# input_output.net
KiCad netlist of a schematic drawn in EAGLE
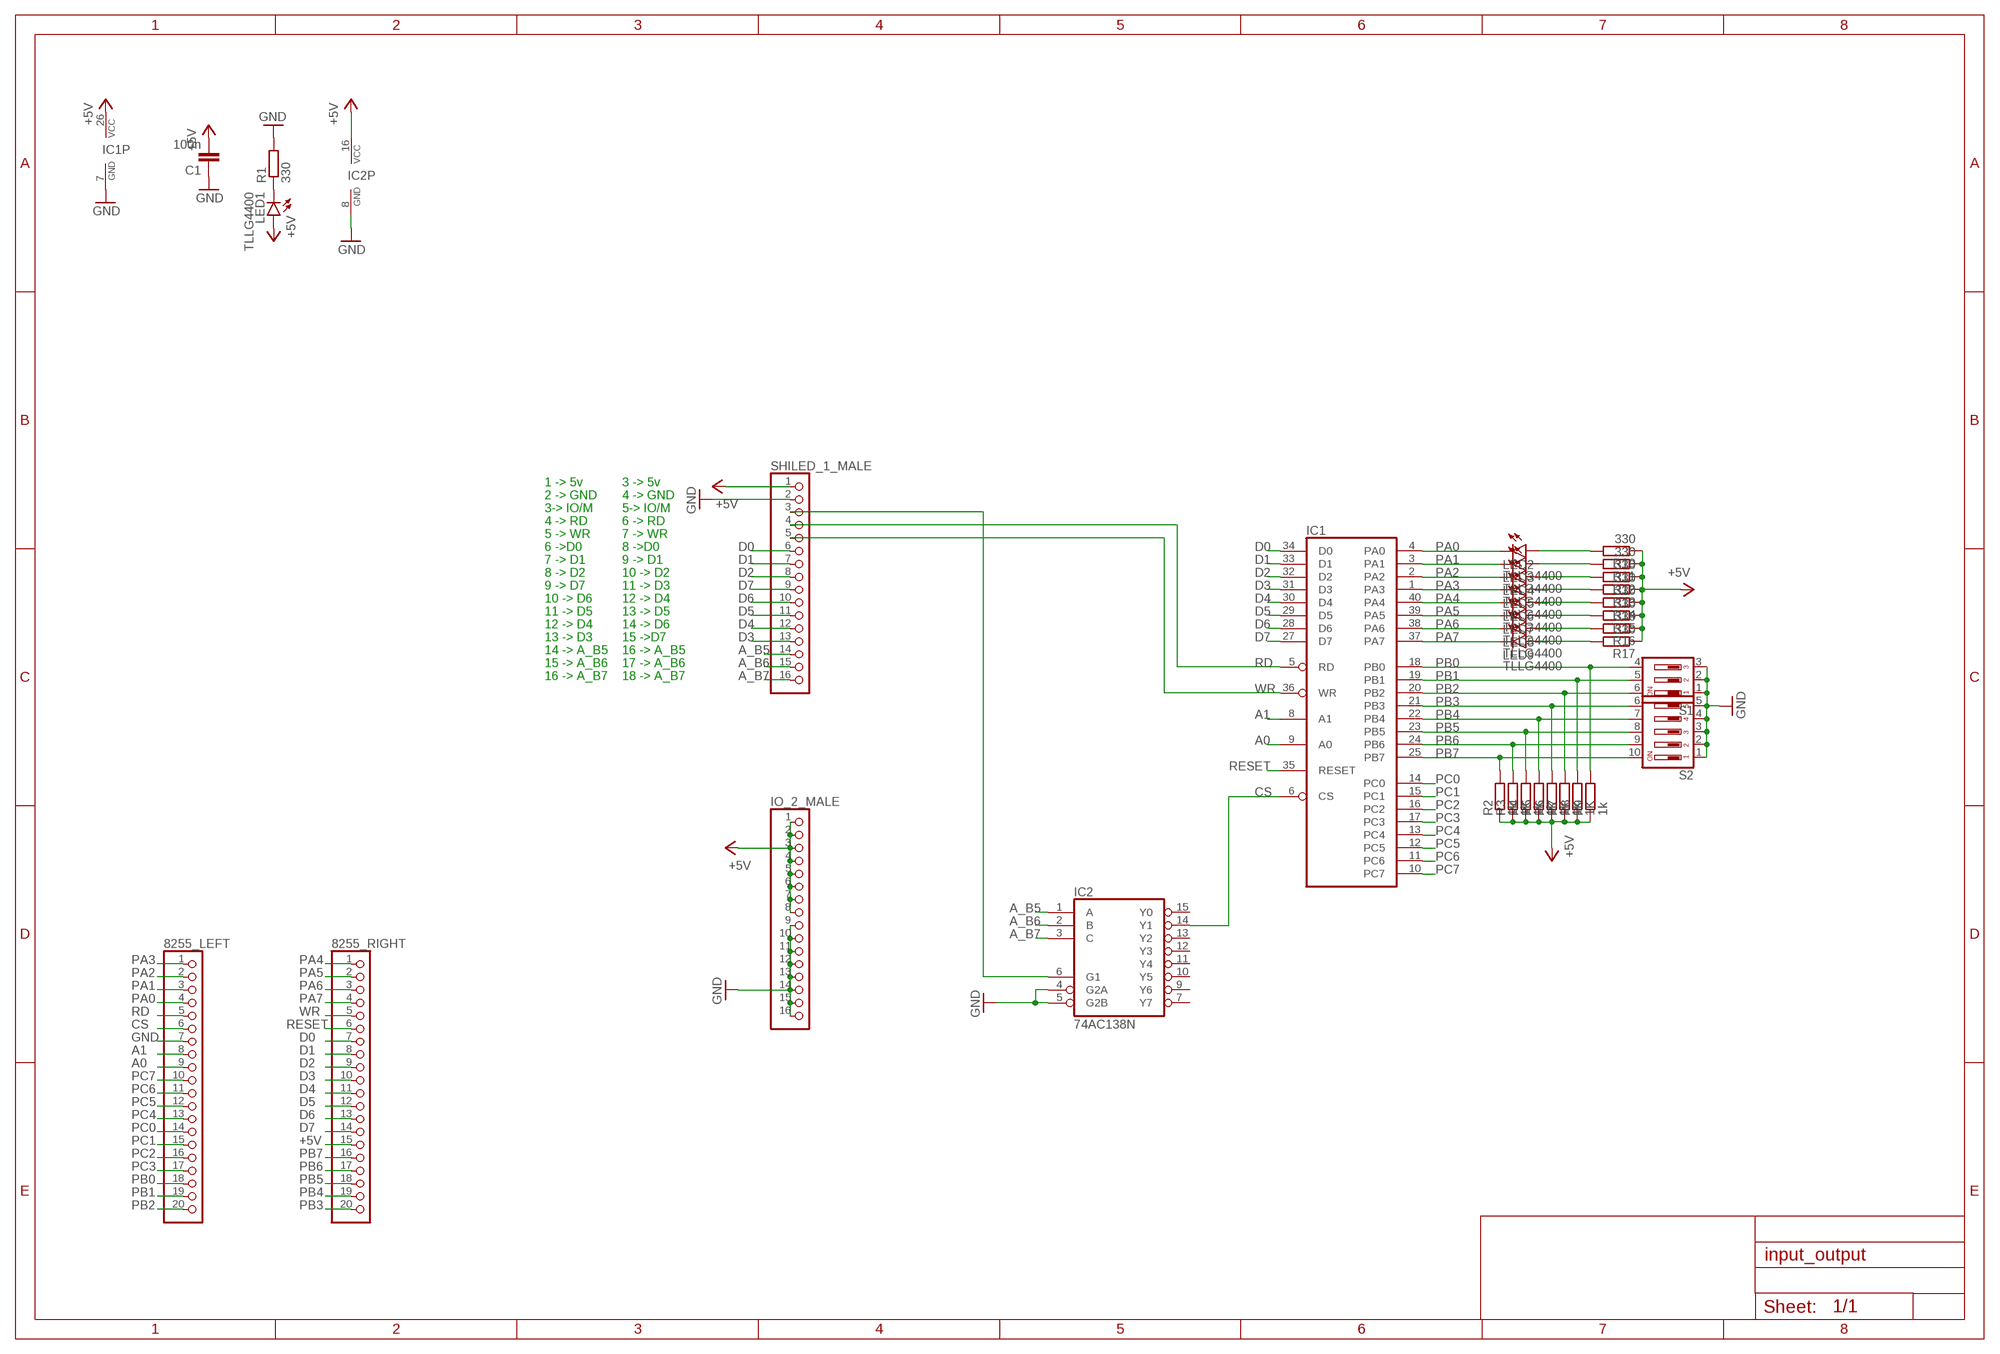
[diagram p0: schematic, sheet 1]

(export (version "E")
  (design (tool "Eeschema 10.0.6"))
  (components
    (comp (ref "8255_LEFT")
      (value "PINHD-1X20")
      (footprint "eagle-import:1X20")
      (libsource (lib "eagle-import") (part "PINHD-1X20"))
    )
    (comp (ref "8255_RIGHT")
      (value "PINHD-1X20")
      (footprint "eagle-import:1X20")
      (libsource (lib "eagle-import") (part "PINHD-1X20"))
    )
    (comp (ref "C1")
      (value "100n")
      (footprint "eagle-import:C025-025X050")
      (libsource (lib "eagle-import") (part "C-EU025-025X050"))
    )
    (comp (ref "IC1")
      (value "8255A")
      (footprint "eagle-import:DIL40")
      (libsource (lib "eagle-import") (part "8255A"))
    )
    (comp (ref "IC2")
      (value "74AC138N")
      (footprint "eagle-import:DIL16")
      (libsource (lib "eagle-import") (part "74138NAC"))
    )
    (comp (ref "IO_2_MALE")
      (value "PINHD-1X16")
      (footprint "eagle-import:1X16")
      (libsource (lib "eagle-import") (part "PINHD-1X16"))
    )
    (comp (ref "LED1")
      (value "TLLG4400")
      (footprint "eagle-import:LED3MM")
      (fields (field (name "MF") "VISHAY SEMICONDUCTOR"))
      (libsource (lib "eagle-import") (part "TLLG4400"))
    )
    (comp (ref "LED2")
      (value "TLLG4400")
      (footprint "eagle-import:LED3MM")
      (fields (field (name "MF") "VISHAY SEMICONDUCTOR"))
      (libsource (lib "eagle-import") (part "TLLG4400"))
    )
    (comp (ref "LED3")
      (value "TLLG4400")
      (footprint "eagle-import:LED3MM")
      (fields (field (name "MF") "VISHAY SEMICONDUCTOR"))
      (libsource (lib "eagle-import") (part "TLLG4400"))
    )
    (comp (ref "LED4")
      (value "TLLG4400")
      (footprint "eagle-import:LED3MM")
      (fields (field (name "MF") "VISHAY SEMICONDUCTOR"))
      (libsource (lib "eagle-import") (part "TLLG4400"))
    )
    (comp (ref "LED5")
      (value "TLLG4400")
      (footprint "eagle-import:LED3MM")
      (fields (field (name "MF") "VISHAY SEMICONDUCTOR"))
      (libsource (lib "eagle-import") (part "TLLG4400"))
    )
    (comp (ref "LED6")
      (value "TLLG4400")
      (footprint "eagle-import:LED3MM")
      (fields (field (name "MF") "VISHAY SEMICONDUCTOR"))
      (libsource (lib "eagle-import") (part "TLLG4400"))
    )
    (comp (ref "LED7")
      (value "TLLG4400")
      (footprint "eagle-import:LED3MM")
      (fields (field (name "MF") "VISHAY SEMICONDUCTOR"))
      (libsource (lib "eagle-import") (part "TLLG4400"))
    )
    (comp (ref "LED8")
      (value "TLLG4400")
      (footprint "eagle-import:LED3MM")
      (fields (field (name "MF") "VISHAY SEMICONDUCTOR"))
      (libsource (lib "eagle-import") (part "TLLG4400"))
    )
    (comp (ref "LED9")
      (value "TLLG4400")
      (footprint "eagle-import:LED3MM")
      (fields (field (name "MF") "VISHAY SEMICONDUCTOR"))
      (libsource (lib "eagle-import") (part "TLLG4400"))
    )
    (comp (ref "R1")
      (value "330")
      (footprint "eagle-import:0207_7")
      (libsource (lib "eagle-import") (part "R-EU_0207/7"))
    )
    (comp (ref "R2")
      (value "1k")
      (footprint "eagle-import:0207_7")
      (libsource (lib "eagle-import") (part "R-EU_0207/7"))
    )
    (comp (ref "R3")
      (value "1k")
      (footprint "eagle-import:0207_7")
      (libsource (lib "eagle-import") (part "R-EU_0207/7"))
    )
    (comp (ref "R4")
      (value "1k")
      (footprint "eagle-import:0207_7")
      (libsource (lib "eagle-import") (part "R-EU_0207/7"))
    )
    (comp (ref "R5")
      (value "1k")
      (footprint "eagle-import:0207_7")
      (libsource (lib "eagle-import") (part "R-EU_0207/7"))
    )
    (comp (ref "R6")
      (value "1k")
      (footprint "eagle-import:0207_7")
      (libsource (lib "eagle-import") (part "R-EU_0207/7"))
    )
    (comp (ref "R7")
      (value "1k")
      (footprint "eagle-import:0207_7")
      (libsource (lib "eagle-import") (part "R-EU_0207/7"))
    )
    (comp (ref "R8")
      (value "1K")
      (footprint "eagle-import:0207_7")
      (libsource (lib "eagle-import") (part "R-EU_0207/7"))
    )
    (comp (ref "R9")
      (value "1k")
      (footprint "eagle-import:0207_7")
      (libsource (lib "eagle-import") (part "R-EU_0207/7"))
    )
    (comp (ref "R10")
      (value "330")
      (footprint "eagle-import:0207_7")
      (libsource (lib "eagle-import") (part "R-EU_0207/7"))
    )
    (comp (ref "R11")
      (value "330")
      (footprint "eagle-import:0207_7")
      (libsource (lib "eagle-import") (part "R-EU_0207/7"))
    )
    (comp (ref "R12")
      (value "330")
      (footprint "eagle-import:0207_7")
      (libsource (lib "eagle-import") (part "R-EU_0207/7"))
    )
    (comp (ref "R13")
      (value "330")
      (footprint "eagle-import:0207_7")
      (libsource (lib "eagle-import") (part "R-EU_0207/7"))
    )
    (comp (ref "R14")
      (value "330")
      (footprint "eagle-import:0207_7")
      (libsource (lib "eagle-import") (part "R-EU_0207/7"))
    )
    (comp (ref "R15")
      (value "330")
      (footprint "eagle-import:0207_7")
      (libsource (lib "eagle-import") (part "R-EU_0207/7"))
    )
    (comp (ref "R16")
      (value "330")
      (footprint "eagle-import:0207_7")
      (libsource (lib "eagle-import") (part "R-EU_0207/7"))
    )
    (comp (ref "R17")
      (value "330")
      (footprint "eagle-import:0207_7")
      (libsource (lib "eagle-import") (part "R-EU_0207/7"))
    )
    (comp (ref "S1")
      (value "DIP03YL")
      (footprint "eagle-import:DIP03YL")
      (libsource (lib "eagle-import") (part "DIP03YL"))
    )
    (comp (ref "S2")
      (value "DIP05YL")
      (footprint "eagle-import:DIP05YL")
      (libsource (lib "eagle-import") (part "DIP05YL"))
    )
    (comp (ref "SHILED_1_MALE")
      (value "PINHD-1X16")
      (footprint "eagle-import:1X16")
      (libsource (lib "eagle-import") (part "PINHD-1X16"))
    )
  )
  (nets
    (net (code "1") (name "+5V") (class "Default")
      (node (ref "8255_RIGHT") (pin "15") (pinfunction "15_15") (pintype "passive"))
      (node (ref "C1") (pin "2") (pinfunction "2_2") (pintype "passive"))
      (node (ref "IC1") (pin "26") (pinfunction "VCC_26") (pintype "power_in"))
      (node (ref "IC2") (pin "16") (pinfunction "VCC_16") (pintype "power_in"))
      (node (ref "IO_2_MALE") (pin "1") (pinfunction "1_1") (pintype "passive"))
      (node (ref "IO_2_MALE") (pin "2") (pinfunction "2_2") (pintype "passive"))
      (node (ref "IO_2_MALE") (pin "3") (pinfunction "3_3") (pintype "passive"))
      (node (ref "IO_2_MALE") (pin "4") (pinfunction "4_4") (pintype "passive"))
      (node (ref "IO_2_MALE") (pin "5") (pinfunction "5_5") (pintype "passive"))
      (node (ref "IO_2_MALE") (pin "6") (pinfunction "6_6") (pintype "passive"))
      (node (ref "IO_2_MALE") (pin "7") (pinfunction "7_7") (pintype "passive"))
      (node (ref "IO_2_MALE") (pin "8") (pinfunction "8_8") (pintype "passive"))
      (node (ref "LED1") (pin "A") (pinfunction "A_A") (pintype "passive"))
      (node (ref "R10") (pin "1") (pinfunction "1_1") (pintype "passive"))
      (node (ref "R11") (pin "1") (pinfunction "1_1") (pintype "passive"))
      (node (ref "R12") (pin "1") (pinfunction "1_1") (pintype "passive"))
      (node (ref "R13") (pin "1") (pinfunction "1_1") (pintype "passive"))
      (node (ref "R14") (pin "1") (pinfunction "1_1") (pintype "passive"))
      (node (ref "R15") (pin "1") (pinfunction "1_1") (pintype "passive"))
      (node (ref "R16") (pin "1") (pinfunction "1_1") (pintype "passive"))
      (node (ref "R17") (pin "1") (pinfunction "1_1") (pintype "passive"))
      (node (ref "R2") (pin "1") (pinfunction "1_1") (pintype "passive"))
      (node (ref "R3") (pin "1") (pinfunction "1_1") (pintype "passive"))
      (node (ref "R4") (pin "1") (pinfunction "1_1") (pintype "passive"))
      (node (ref "R5") (pin "1") (pinfunction "1_1") (pintype "passive"))
      (node (ref "R6") (pin "1") (pinfunction "1_1") (pintype "passive"))
      (node (ref "R7") (pin "1") (pinfunction "1_1") (pintype "passive"))
      (node (ref "R8") (pin "1") (pinfunction "1_1") (pintype "passive"))
      (node (ref "R9") (pin "1") (pinfunction "1_1") (pintype "passive"))
      (node (ref "SHILED_1_MALE") (pin "1") (pinfunction "1_1") (pintype "passive"))
    )
    (net (code "2") (name "/A0") (class "Default")
      (node (ref "8255_LEFT") (pin "9") (pinfunction "9_9") (pintype "passive"))
      (node (ref "IC1") (pin "9") (pinfunction "A0_9") (pintype "input"))
    )
    (net (code "3") (name "/A1") (class "Default")
      (node (ref "8255_LEFT") (pin "8") (pinfunction "8_8") (pintype "passive"))
      (node (ref "IC1") (pin "8") (pinfunction "A1_8") (pintype "input"))
    )
    (net (code "4") (name "/A_B5") (class "Default")
      (node (ref "IC2") (pin "1") (pinfunction "A_1") (pintype "input"))
      (node (ref "SHILED_1_MALE") (pin "14") (pinfunction "14_14") (pintype "passive"))
    )
    (net (code "5") (name "/A_B6") (class "Default")
      (node (ref "IC2") (pin "2") (pinfunction "B_2") (pintype "input"))
      (node (ref "SHILED_1_MALE") (pin "15") (pinfunction "15_15") (pintype "passive"))
    )
    (net (code "6") (name "/A_B7") (class "Default")
      (node (ref "IC2") (pin "3") (pinfunction "C_3") (pintype "input"))
      (node (ref "SHILED_1_MALE") (pin "16") (pinfunction "16_16") (pintype "passive"))
    )
    (net (code "7") (name "/CS") (class "Default")
      (node (ref "8255_LEFT") (pin "6") (pinfunction "6_6") (pintype "passive"))
      (node (ref "IC1") (pin "6") (pinfunction "CS_6") (pintype "input"))
      (node (ref "IC2") (pin "14") (pinfunction "Y1_14") (pintype "output"))
    )
    (net (code "8") (name "/D0") (class "Default")
      (node (ref "8255_RIGHT") (pin "7") (pinfunction "7_7") (pintype "passive"))
      (node (ref "IC1") (pin "34") (pinfunction "D0_34") (pintype "bidirectional"))
      (node (ref "SHILED_1_MALE") (pin "6") (pinfunction "6_6") (pintype "passive"))
    )
    (net (code "9") (name "/D1") (class "Default")
      (node (ref "8255_RIGHT") (pin "8") (pinfunction "8_8") (pintype "passive"))
      (node (ref "IC1") (pin "33") (pinfunction "D1_33") (pintype "bidirectional"))
      (node (ref "SHILED_1_MALE") (pin "7") (pinfunction "7_7") (pintype "passive"))
    )
    (net (code "10") (name "/D2") (class "Default")
      (node (ref "8255_RIGHT") (pin "9") (pinfunction "9_9") (pintype "passive"))
      (node (ref "IC1") (pin "32") (pinfunction "D2_32") (pintype "bidirectional"))
      (node (ref "SHILED_1_MALE") (pin "8") (pinfunction "8_8") (pintype "passive"))
    )
    (net (code "11") (name "/D3") (class "Default")
      (node (ref "8255_RIGHT") (pin "10") (pinfunction "10_10") (pintype "passive"))
      (node (ref "IC1") (pin "31") (pinfunction "D3_31") (pintype "bidirectional"))
      (node (ref "SHILED_1_MALE") (pin "13") (pinfunction "13_13") (pintype "passive"))
    )
    (net (code "12") (name "/D4") (class "Default")
      (node (ref "8255_RIGHT") (pin "11") (pinfunction "11_11") (pintype "passive"))
      (node (ref "IC1") (pin "30") (pinfunction "D4_30") (pintype "bidirectional"))
      (node (ref "SHILED_1_MALE") (pin "12") (pinfunction "12_12") (pintype "passive"))
    )
    (net (code "13") (name "/D5") (class "Default")
      (node (ref "8255_RIGHT") (pin "12") (pinfunction "12_12") (pintype "passive"))
      (node (ref "IC1") (pin "29") (pinfunction "D5_29") (pintype "bidirectional"))
      (node (ref "SHILED_1_MALE") (pin "11") (pinfunction "11_11") (pintype "passive"))
    )
    (net (code "14") (name "/D6") (class "Default")
      (node (ref "8255_RIGHT") (pin "13") (pinfunction "13_13") (pintype "passive"))
      (node (ref "IC1") (pin "28") (pinfunction "D6_28") (pintype "bidirectional"))
      (node (ref "SHILED_1_MALE") (pin "10") (pinfunction "10_10") (pintype "passive"))
    )
    (net (code "15") (name "/D7") (class "Default")
      (node (ref "8255_RIGHT") (pin "14") (pinfunction "14_14") (pintype "passive"))
      (node (ref "IC1") (pin "27") (pinfunction "D7_27") (pintype "bidirectional"))
      (node (ref "SHILED_1_MALE") (pin "9") (pinfunction "9_9") (pintype "passive"))
    )
    (net (code "16") (name "/PA0") (class "Default")
      (node (ref "8255_LEFT") (pin "4") (pinfunction "4_4") (pintype "passive"))
      (node (ref "IC1") (pin "4") (pinfunction "PA0_4") (pintype "bidirectional"))
      (node (ref "LED2") (pin "K") (pinfunction "C_K") (pintype "passive"))
    )
    (net (code "17") (name "/PA1") (class "Default")
      (node (ref "8255_LEFT") (pin "3") (pinfunction "3_3") (pintype "passive"))
      (node (ref "IC1") (pin "3") (pinfunction "PA1_3") (pintype "bidirectional"))
      (node (ref "LED3") (pin "K") (pinfunction "C_K") (pintype "passive"))
    )
    (net (code "18") (name "/PA2") (class "Default")
      (node (ref "8255_LEFT") (pin "2") (pinfunction "2_2") (pintype "passive"))
      (node (ref "IC1") (pin "2") (pinfunction "PA2_2") (pintype "bidirectional"))
      (node (ref "LED4") (pin "K") (pinfunction "C_K") (pintype "passive"))
    )
    (net (code "19") (name "/PA3") (class "Default")
      (node (ref "8255_LEFT") (pin "1") (pinfunction "1_1") (pintype "passive"))
      (node (ref "IC1") (pin "1") (pinfunction "PA3_1") (pintype "bidirectional"))
      (node (ref "LED5") (pin "K") (pinfunction "C_K") (pintype "passive"))
    )
    (net (code "20") (name "/PA4") (class "Default")
      (node (ref "8255_RIGHT") (pin "1") (pinfunction "1_1") (pintype "passive"))
      (node (ref "IC1") (pin "40") (pinfunction "PA4_40") (pintype "bidirectional"))
      (node (ref "LED6") (pin "K") (pinfunction "C_K") (pintype "passive"))
    )
    (net (code "21") (name "/PA5") (class "Default")
      (node (ref "8255_RIGHT") (pin "2") (pinfunction "2_2") (pintype "passive"))
      (node (ref "IC1") (pin "39") (pinfunction "PA5_39") (pintype "bidirectional"))
      (node (ref "LED7") (pin "K") (pinfunction "C_K") (pintype "passive"))
    )
    (net (code "22") (name "/PA6") (class "Default")
      (node (ref "8255_RIGHT") (pin "3") (pinfunction "3_3") (pintype "passive"))
      (node (ref "IC1") (pin "38") (pinfunction "PA6_38") (pintype "bidirectional"))
      (node (ref "LED8") (pin "K") (pinfunction "C_K") (pintype "passive"))
    )
    (net (code "23") (name "/PA7") (class "Default")
      (node (ref "8255_RIGHT") (pin "4") (pinfunction "4_4") (pintype "passive"))
      (node (ref "IC1") (pin "37") (pinfunction "PA7_37") (pintype "bidirectional"))
      (node (ref "LED9") (pin "K") (pinfunction "C_K") (pintype "passive"))
    )
    (net (code "24") (name "/PB0") (class "Default")
      (node (ref "8255_LEFT") (pin "18") (pinfunction "18_18") (pintype "passive"))
      (node (ref "IC1") (pin "18") (pinfunction "PB0_18") (pintype "bidirectional"))
      (node (ref "R9") (pin "2") (pinfunction "2_2") (pintype "passive"))
      (node (ref "S1") (pin "4") (pinfunction "4_4") (pintype "passive"))
    )
    (net (code "25") (name "/PB1") (class "Default")
      (node (ref "8255_LEFT") (pin "19") (pinfunction "19_19") (pintype "passive"))
      (node (ref "IC1") (pin "19") (pinfunction "PB1_19") (pintype "bidirectional"))
      (node (ref "R8") (pin "2") (pinfunction "2_2") (pintype "passive"))
      (node (ref "S1") (pin "5") (pinfunction "5_5") (pintype "passive"))
    )
    (net (code "26") (name "/PB2") (class "Default")
      (node (ref "8255_LEFT") (pin "20") (pinfunction "20_20") (pintype "passive"))
      (node (ref "IC1") (pin "20") (pinfunction "PB2_20") (pintype "bidirectional"))
      (node (ref "R7") (pin "2") (pinfunction "2_2") (pintype "passive"))
      (node (ref "S1") (pin "6") (pinfunction "6_6") (pintype "passive"))
    )
    (net (code "27") (name "/PB3") (class "Default")
      (node (ref "8255_RIGHT") (pin "20") (pinfunction "20_20") (pintype "passive"))
      (node (ref "IC1") (pin "21") (pinfunction "PB3_21") (pintype "bidirectional"))
      (node (ref "R6") (pin "2") (pinfunction "2_2") (pintype "passive"))
      (node (ref "S2") (pin "6") (pinfunction "6_6") (pintype "passive"))
    )
    (net (code "28") (name "/PB4") (class "Default")
      (node (ref "8255_RIGHT") (pin "19") (pinfunction "19_19") (pintype "passive"))
      (node (ref "IC1") (pin "22") (pinfunction "PB4_22") (pintype "bidirectional"))
      (node (ref "R5") (pin "2") (pinfunction "2_2") (pintype "passive"))
      (node (ref "S2") (pin "7") (pinfunction "7_7") (pintype "passive"))
    )
    (net (code "29") (name "/PB5") (class "Default")
      (node (ref "8255_RIGHT") (pin "18") (pinfunction "18_18") (pintype "passive"))
      (node (ref "IC1") (pin "23") (pinfunction "PB5_23") (pintype "bidirectional"))
      (node (ref "R4") (pin "2") (pinfunction "2_2") (pintype "passive"))
      (node (ref "S2") (pin "8") (pinfunction "8_8") (pintype "passive"))
    )
    (net (code "30") (name "/PB6") (class "Default")
      (node (ref "8255_RIGHT") (pin "17") (pinfunction "17_17") (pintype "passive"))
      (node (ref "IC1") (pin "24") (pinfunction "PB6_24") (pintype "bidirectional"))
      (node (ref "R3") (pin "2") (pinfunction "2_2") (pintype "passive"))
      (node (ref "S2") (pin "9") (pinfunction "9_9") (pintype "passive"))
    )
    (net (code "31") (name "/PB7") (class "Default")
      (node (ref "8255_RIGHT") (pin "16") (pinfunction "16_16") (pintype "passive"))
      (node (ref "IC1") (pin "25") (pinfunction "PB7_25") (pintype "bidirectional"))
      (node (ref "R2") (pin "2") (pinfunction "2_2") (pintype "passive"))
      (node (ref "S2") (pin "10") (pinfunction "10_10") (pintype "passive"))
    )
    (net (code "32") (name "/PC0") (class "Default")
      (node (ref "8255_LEFT") (pin "14") (pinfunction "14_14") (pintype "passive"))
      (node (ref "IC1") (pin "14") (pinfunction "PC0_14") (pintype "bidirectional"))
    )
    (net (code "33") (name "/PC1") (class "Default")
      (node (ref "8255_LEFT") (pin "15") (pinfunction "15_15") (pintype "passive"))
      (node (ref "IC1") (pin "15") (pinfunction "PC1_15") (pintype "bidirectional"))
    )
    (net (code "34") (name "/PC2") (class "Default")
      (node (ref "8255_LEFT") (pin "16") (pinfunction "16_16") (pintype "passive"))
      (node (ref "IC1") (pin "16") (pinfunction "PC2_16") (pintype "bidirectional"))
    )
    (net (code "35") (name "/PC3") (class "Default")
      (node (ref "8255_LEFT") (pin "17") (pinfunction "17_17") (pintype "passive"))
      (node (ref "IC1") (pin "17") (pinfunction "PC3_17") (pintype "bidirectional"))
    )
    (net (code "36") (name "/PC4") (class "Default")
      (node (ref "8255_LEFT") (pin "13") (pinfunction "13_13") (pintype "passive"))
      (node (ref "IC1") (pin "13") (pinfunction "PC4_13") (pintype "bidirectional"))
    )
    (net (code "37") (name "/PC5") (class "Default")
      (node (ref "8255_LEFT") (pin "12") (pinfunction "12_12") (pintype "passive"))
      (node (ref "IC1") (pin "12") (pinfunction "PC5_12") (pintype "bidirectional"))
    )
    (net (code "38") (name "/PC6") (class "Default")
      (node (ref "8255_LEFT") (pin "11") (pinfunction "11_11") (pintype "passive"))
      (node (ref "IC1") (pin "11") (pinfunction "PC6_11") (pintype "bidirectional"))
    )
    (net (code "39") (name "/PC7") (class "Default")
      (node (ref "8255_LEFT") (pin "10") (pinfunction "10_10") (pintype "passive"))
      (node (ref "IC1") (pin "10") (pinfunction "PC7_10") (pintype "bidirectional"))
    )
    (net (code "40") (name "/RD") (class "Default")
      (node (ref "8255_LEFT") (pin "5") (pinfunction "5_5") (pintype "passive"))
      (node (ref "IC1") (pin "5") (pinfunction "RD_5") (pintype "input"))
      (node (ref "SHILED_1_MALE") (pin "4") (pinfunction "4_4") (pintype "passive"))
    )
    (net (code "41") (name "/RESET") (class "Default")
      (node (ref "8255_RIGHT") (pin "6") (pinfunction "6_6") (pintype "passive"))
      (node (ref "IC1") (pin "35") (pinfunction "RESET_35") (pintype "input"))
    )
    (net (code "42") (name "/WR") (class "Default")
      (node (ref "8255_RIGHT") (pin "5") (pinfunction "5_5") (pintype "passive"))
      (node (ref "IC1") (pin "36") (pinfunction "WR_36") (pintype "input"))
      (node (ref "SHILED_1_MALE") (pin "5") (pinfunction "5_5") (pintype "passive"))
    )
    (net (code "43") (name "GND") (class "Default")
      (node (ref "8255_LEFT") (pin "7") (pinfunction "7_7") (pintype "passive"))
      (node (ref "C1") (pin "1") (pinfunction "1_1") (pintype "passive"))
      (node (ref "IC1") (pin "7") (pinfunction "GND_7") (pintype "power_in"))
      (node (ref "IC2") (pin "4") (pinfunction "G2A_4") (pintype "input"))
      (node (ref "IC2") (pin "5") (pinfunction "G2B_5") (pintype "input"))
      (node (ref "IC2") (pin "8") (pinfunction "GND_8") (pintype "power_in"))
      (node (ref "IO_2_MALE") (pin "10") (pinfunction "10_10") (pintype "passive"))
      (node (ref "IO_2_MALE") (pin "11") (pinfunction "11_11") (pintype "passive"))
      (node (ref "IO_2_MALE") (pin "12") (pinfunction "12_12") (pintype "passive"))
      (node (ref "IO_2_MALE") (pin "13") (pinfunction "13_13") (pintype "passive"))
      (node (ref "IO_2_MALE") (pin "14") (pinfunction "14_14") (pintype "passive"))
      (node (ref "IO_2_MALE") (pin "15") (pinfunction "15_15") (pintype "passive"))
      (node (ref "IO_2_MALE") (pin "16") (pinfunction "16_16") (pintype "passive"))
      (node (ref "IO_2_MALE") (pin "9") (pinfunction "9_9") (pintype "passive"))
      (node (ref "R1") (pin "2") (pinfunction "2_2") (pintype "passive"))
      (node (ref "S1") (pin "1") (pinfunction "1_1") (pintype "passive"))
      (node (ref "S1") (pin "2") (pinfunction "2_2") (pintype "passive"))
      (node (ref "S1") (pin "3") (pinfunction "3_3") (pintype "passive"))
      (node (ref "S2") (pin "1") (pinfunction "1_1") (pintype "passive"))
      (node (ref "S2") (pin "2") (pinfunction "2_2") (pintype "passive"))
      (node (ref "S2") (pin "3") (pinfunction "3_3") (pintype "passive"))
      (node (ref "S2") (pin "4") (pinfunction "4_4") (pintype "passive"))
      (node (ref "S2") (pin "5") (pinfunction "5_5") (pintype "passive"))
      (node (ref "SHILED_1_MALE") (pin "2") (pinfunction "2_2") (pintype "passive"))
    )
    (net (code "44") (name "Net-(IC2A-G1)") (class "Default")
      (node (ref "IC2") (pin "6") (pinfunction "G1_6") (pintype "input"))
      (node (ref "SHILED_1_MALE") (pin "3") (pinfunction "3_3") (pintype "passive"))
    )
    (net (code "45") (name "Net-(LED1-C)") (class "Default")
      (node (ref "LED1") (pin "K") (pinfunction "C_K") (pintype "passive"))
      (node (ref "R1") (pin "1") (pinfunction "1_1") (pintype "passive"))
    )
    (net (code "46") (name "Net-(LED2-PadA)") (class "Default")
      (node (ref "LED2") (pin "A") (pinfunction "A_A") (pintype "passive"))
      (node (ref "R10") (pin "2") (pinfunction "2_2") (pintype "passive"))
    )
    (net (code "47") (name "Net-(LED3-PadA)") (class "Default")
      (node (ref "LED3") (pin "A") (pinfunction "A_A") (pintype "passive"))
      (node (ref "R11") (pin "2") (pinfunction "2_2") (pintype "passive"))
    )
    (net (code "48") (name "Net-(LED4-PadA)") (class "Default")
      (node (ref "LED4") (pin "A") (pinfunction "A_A") (pintype "passive"))
      (node (ref "R12") (pin "2") (pinfunction "2_2") (pintype "passive"))
    )
    (net (code "49") (name "Net-(LED5-PadA)") (class "Default")
      (node (ref "LED5") (pin "A") (pinfunction "A_A") (pintype "passive"))
      (node (ref "R13") (pin "2") (pinfunction "2_2") (pintype "passive"))
    )
    (net (code "50") (name "Net-(LED6-PadA)") (class "Default")
      (node (ref "LED6") (pin "A") (pinfunction "A_A") (pintype "passive"))
      (node (ref "R14") (pin "2") (pinfunction "2_2") (pintype "passive"))
    )
    (net (code "51") (name "Net-(LED7-PadA)") (class "Default")
      (node (ref "LED7") (pin "A") (pinfunction "A_A") (pintype "passive"))
      (node (ref "R15") (pin "2") (pinfunction "2_2") (pintype "passive"))
    )
    (net (code "52") (name "Net-(LED8-PadA)") (class "Default")
      (node (ref "LED8") (pin "A") (pinfunction "A_A") (pintype "passive"))
      (node (ref "R16") (pin "2") (pinfunction "2_2") (pintype "passive"))
    )
    (net (code "53") (name "Net-(LED9-PadA)") (class "Default")
      (node (ref "LED9") (pin "A") (pinfunction "A_A") (pintype "passive"))
      (node (ref "R17") (pin "2") (pinfunction "2_2") (pintype "passive"))
    )
    (net (code "54") (name "unconnected-(IC2A-Y0-Pad15)") (class "Default")
      (node (ref "IC2") (pin "15") (pinfunction "Y0_15") (pintype "output"))
    )
    (net (code "55") (name "unconnected-(IC2A-Y2-Pad13)") (class "Default")
      (node (ref "IC2") (pin "13") (pinfunction "Y2_13") (pintype "output"))
    )
    (net (code "56") (name "unconnected-(IC2A-Y3-Pad12)") (class "Default")
      (node (ref "IC2") (pin "12") (pinfunction "Y3_12") (pintype "output"))
    )
    (net (code "57") (name "unconnected-(IC2A-Y4-Pad11)") (class "Default")
      (node (ref "IC2") (pin "11") (pinfunction "Y4_11") (pintype "output"))
    )
    (net (code "58") (name "unconnected-(IC2A-Y5-Pad10)") (class "Default")
      (node (ref "IC2") (pin "10") (pinfunction "Y5_10") (pintype "output"))
    )
    (net (code "59") (name "unconnected-(IC2A-Y6-Pad9)") (class "Default")
      (node (ref "IC2") (pin "9") (pinfunction "Y6_9") (pintype "output"))
    )
    (net (code "60") (name "unconnected-(IC2A-Y7-Pad7)") (class "Default")
      (node (ref "IC2") (pin "7") (pinfunction "Y7_7") (pintype "output"))
    )
  )
)
